# POWER.net
KiCad netlist of a schematic drawn in Altium Designer
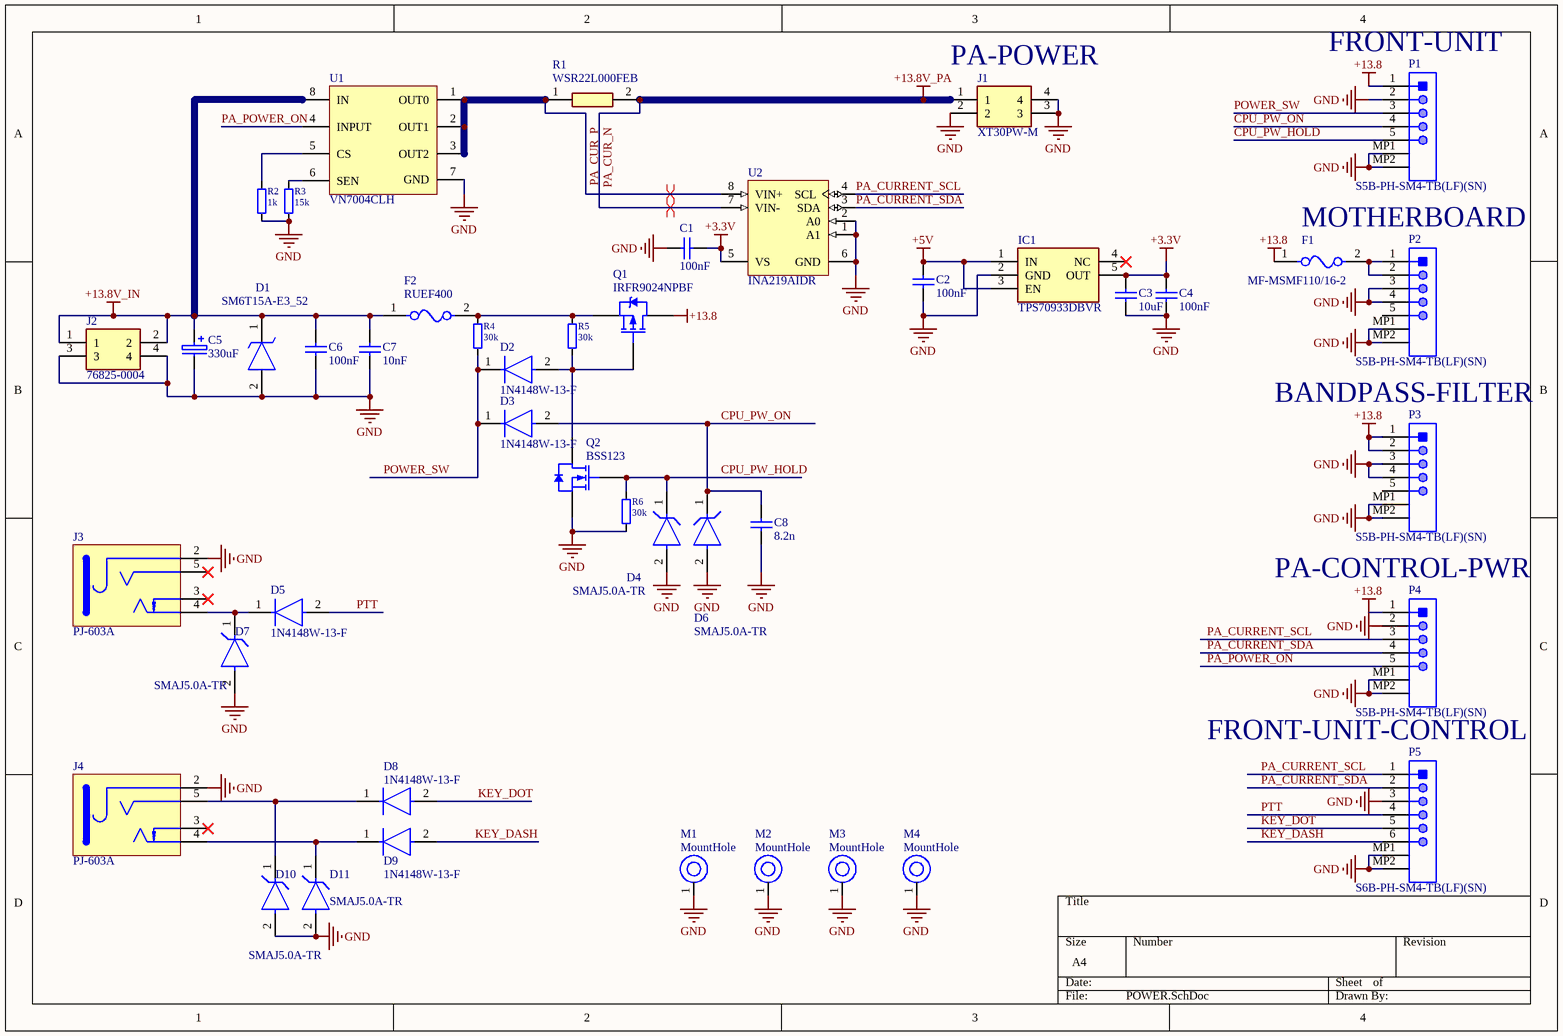
[diagram p0: POWER.SchDoc]

(export (version "E")
  (design (tool "Eeschema 10.0.6"))
  (components
    (comp (ref "C1")
      (value "100nF")
      (footprint "C-0805")
      (description "Ceramic Multilayer Capacitor")
      (fields (field (name "MANUFACTURER") "Yageo/Phycomp") (field (name "TOLERANCE") "±10%"))
      (libsource (lib "Hristo") (part "C semi"))
    )
    (comp (ref "C2")
      (value "100nF")
      (footprint "C-0805")
      (description "Ceramic Multilayer Capacitor")
      (fields (field (name "MANUFACTURER") "Yageo/Phycomp") (field (name "TOLERANCE") "±10%"))
      (libsource (lib "Hristo") (part "C semi"))
    )
    (comp (ref "C3")
      (value "10uF")
      (footprint "C-0805")
      (description "Ceramic Multilayer Capacitor")
      (fields (field (name "MANUFACTURER") "Yageo/Phycomp") (field (name "TOLERANCE") "±10%"))
      (libsource (lib "Hristo") (part "C semi"))
    )
    (comp (ref "C4")
      (value "100nF")
      (footprint "C-0805")
      (description "Ceramic Multilayer Capacitor")
      (fields (field (name "MANUFACTURER") "Yageo/Phycomp") (field (name "TOLERANCE") "±10%"))
      (libsource (lib "Hristo") (part "C semi"))
    )
    (comp (ref "C5")
      (value "330uF")
      (footprint "CE 5.0-10x12.5")
      (description "Capacitor Electrolytic")
      (fields (field (name "MANUFACTURER") "Yageo/Phycomp") (field (name "TOLERANCE") "±20%"))
      (libsource (lib "Hristo") (part "CE"))
    )
    (comp (ref "C6")
      (value "100nF")
      (footprint "C-0805")
      (description "Ceramic Multilayer Capacitor")
      (fields (field (name "MANUFACTURER") "Yageo/Phycomp") (field (name "TOLERANCE") "±10%"))
      (libsource (lib "Hristo") (part "C semi"))
    )
    (comp (ref "C7")
      (value "10nF")
      (footprint "C-0805")
      (description "Ceramic Multilayer Capacitor")
      (fields (field (name "MANUFACTURER") "Yageo/Phycomp") (field (name "TOLERANCE") "±10%"))
      (libsource (lib "Hristo") (part "C semi"))
    )
    (comp (ref "C8")
      (value "8.2n")
      (footprint "C-0805")
      (description "Ceramic Multilayer Capacitor")
      (fields (field (name "MANUFACTURER") "Yageo/Phycomp") (field (name "TOLERANCE") "±10%"))
      (libsource (lib "Hristo") (part "C semi"))
    )
    (comp (ref "D1")
      (value "SM6T15A-E3_52")
      (footprint "SamacSys:DIOM5436X244N")
      (description "TVS Diode (Uni-directional)")
      (fields
        (field (name "MANUFACTURER_PART_NUMBER") "SM6T15A-E3/52")
        (field (name "MOUSER PART NUMBER") "625-SM6T15A-E3")
      )
      (libsource (lib "*") (part "SM6T15A-E3_52"))
    )
    (comp (ref "D2")
      (value "1N4148W-13-F")
      (footprint "FP-SOD123-MFG")
      (description "DIODE GEN PURP 100V 150MA SOD123")
      (fields
        (field (name "OCTOPART") "https://octopart.com/1n4148w-13-f-diodes+inc.-2359612")
        (field (name "MANUFACTURER") "Diodes Inc.")
      )
      (libsource (lib "Altium Content Vault") (part "d7152d700b627762746794eb795d46e"))
    )
    (comp (ref "D3")
      (value "1N4148W-13-F")
      (footprint "FP-SOD123-MFG")
      (description "DIODE GEN PURP 100V 150MA SOD123")
      (fields
        (field (name "OCTOPART") "https://octopart.com/1n4148w-13-f-diodes+inc.-2359612")
        (field (name "MANUFACTURER") "Diodes Inc.")
      )
      (libsource (lib "Altium Content Vault") (part "d7152d700b627762746794eb795d46e"))
    )
    (comp (ref "D4")
      (value "SMAJ5.0A-TR")
      (footprint "FP-SMA-MFG")
      (description "TVS DIODE 5V 13.4V SMA")
      (fields
        (field (name "MANUFACTURER") "STMicroelectronics")
        (field (name "OCTOPART") "https://octopart.com/smaj5.0a-tr-stmicroelectronics-347063")
      )
      (libsource (lib "Altium Content Vault") (part "7ddec9f632b8482e96f7745d0fbdf39"))
    )
    (comp (ref "D5")
      (value "1N4148W-13-F")
      (footprint "FP-SOD123-MFG")
      (description "DIODE GEN PURP 100V 150MA SOD123")
      (fields
        (field (name "OCTOPART") "https://octopart.com/1n4148w-13-f-diodes+inc.-2359612")
        (field (name "MANUFACTURER") "Diodes Inc.")
      )
      (libsource (lib "Altium Content Vault") (part "d7152d700b627762746794eb795d46e"))
    )
    (comp (ref "D6")
      (value "SMAJ5.0A-TR")
      (footprint "FP-SMA-MFG")
      (description "TVS DIODE 5V 13.4V SMA")
      (fields
        (field (name "MANUFACTURER") "STMicroelectronics")
        (field (name "OCTOPART") "https://octopart.com/smaj5.0a-tr-stmicroelectronics-347063")
      )
      (libsource (lib "Altium Content Vault") (part "7ddec9f632b8482e96f7745d0fbdf39"))
    )
    (comp (ref "D7")
      (value "SMAJ5.0A-TR")
      (footprint "FP-SMA-MFG")
      (description "TVS DIODE 5V 13.4V SMA")
      (fields
        (field (name "MANUFACTURER") "STMicroelectronics")
        (field (name "OCTOPART") "https://octopart.com/smaj5.0a-tr-stmicroelectronics-347063")
      )
      (libsource (lib "Altium Content Vault") (part "7ddec9f632b8482e96f7745d0fbdf39"))
    )
    (comp (ref "D8")
      (value "1N4148W-13-F")
      (footprint "FP-SOD123-MFG")
      (description "DIODE GEN PURP 100V 150MA SOD123")
      (fields
        (field (name "OCTOPART") "https://octopart.com/1n4148w-13-f-diodes+inc.-2359612")
        (field (name "MANUFACTURER") "Diodes Inc.")
      )
      (libsource (lib "Altium Content Vault") (part "d7152d700b627762746794eb795d46e"))
    )
    (comp (ref "D9")
      (value "1N4148W-13-F")
      (footprint "FP-SOD123-MFG")
      (description "DIODE GEN PURP 100V 150MA SOD123")
      (fields
        (field (name "OCTOPART") "https://octopart.com/1n4148w-13-f-diodes+inc.-2359612")
        (field (name "MANUFACTURER") "Diodes Inc.")
      )
      (libsource (lib "Altium Content Vault") (part "d7152d700b627762746794eb795d46e"))
    )
    (comp (ref "D10")
      (value "SMAJ5.0A-TR")
      (footprint "FP-SMA-MFG")
      (description "TVS DIODE 5V 13.4V SMA")
      (fields
        (field (name "MANUFACTURER") "STMicroelectronics")
        (field (name "OCTOPART") "https://octopart.com/smaj5.0a-tr-stmicroelectronics-347063")
      )
      (libsource (lib "Altium Content Vault") (part "7ddec9f632b8482e96f7745d0fbdf39"))
    )
    (comp (ref "D11")
      (value "SMAJ5.0A-TR")
      (footprint "FP-SMA-MFG")
      (description "TVS DIODE 5V 13.4V SMA")
      (fields
        (field (name "MANUFACTURER") "STMicroelectronics")
        (field (name "OCTOPART") "https://octopart.com/smaj5.0a-tr-stmicroelectronics-347063")
      )
      (libsource (lib "Altium Content Vault") (part "7ddec9f632b8482e96f7745d0fbdf39"))
    )
    (comp (ref "F1")
      (value "MF-MSMF110/16-2")
      (footprint "FP-MF-MSMF110-16-MFG")
      (description "PTC RESET FUSE 16V 1.1A 1812")
      (fields
        (field (name "OCTOPART") "https://octopart.com/mf-msmf110%2F16-2-bourns-40767")
        (field (name "MANUFACTURER") "Bourns")
      )
      (libsource (lib "Altium Content Vault") (part "5bcf9b9f640e542cf0359d10258e979"))
    )
    (comp (ref "F2")
      (value "RUEF400")
      (footprint "FP-RUEF400-MFG")
      (description "PTC RESET FUSE 30V 4A RADIAL")
      (fields
        (field (name "MANUFACTURER") "Littelfuse")
        (field (name "OCTOPART") "https://octopart.com/ruef400-littelfuse-74215791")
      )
      (libsource (lib "Altium Content Vault") (part "5bcf9b9f640e542cf0359d10258e979"))
    )
    (comp (ref "IC1")
      (value "TPS70933DBVR")
      (footprint "SamacSys:SOT95P280X145-5N")
      (description "Integrated Circuit")
      (fields (field (name "MOUSER PART NUMBER") "595-TPS70933DBVR"))
      (libsource (lib "*") (part "TPS70933DBVR"))
    )
    (comp (ref "J1")
      (value "XT30PW-M")
      (footprint "SamacSys:XT30PWM")
      (description "Connector")
      (libsource (lib "*") (part "XT30PW-M"))
    )
    (comp (ref "J2")
      (value "76825-0004")
      (footprint "SamacSys:768250004")
      (description "Connector")
      (fields (field (name "MOUSER2 PART NUMBER") "538-76825-0004"))
      (libsource (lib "*") (part "76825-0004"))
    )
    (comp (ref "J3") (value "PJ-603A") (footprint "PJ-603A") (libsource (lib "Hristo") (part "PJ-603A")))
    (comp (ref "J4") (value "PJ-603A") (footprint "PJ-603A") (libsource (lib "Hristo") (part "PJ-603A")))
    (comp (ref "M1")
      (value "MountHole")
      (footprint "MountHole")
      (libsource (lib "Hristo") (part "MountHole"))
    )
    (comp (ref "M2")
      (value "MountHole")
      (footprint "MountHole")
      (libsource (lib "Hristo") (part "MountHole"))
    )
    (comp (ref "M3")
      (value "MountHole")
      (footprint "MountHole")
      (libsource (lib "Hristo") (part "MountHole"))
    )
    (comp (ref "M4")
      (value "MountHole")
      (footprint "MountHole")
      (libsource (lib "Hristo") (part "MountHole"))
    )
    (comp (ref "P1")
      (value "S5B-PH-SM4-TB(LF)(SN)")
      (footprint "JST-S5B-PH-SM4-TB_V")
      (description "Male Header, Pitch 2 mm, 1 x 5 Position, Height 5.5 mm, -25 to 85 degC, RoHS, Tape and Reel")
      (fields (field (name "MANUFACTURER") "JST"))
      (libsource (lib "Altium Content Vault") (part "CN-1P-2M-R5"))
    )
    (comp (ref "P2")
      (value "S5B-PH-SM4-TB(LF)(SN)")
      (footprint "JST-S5B-PH-SM4-TB_V")
      (description "Male Header, Pitch 2 mm, 1 x 5 Position, Height 5.5 mm, -25 to 85 degC, RoHS, Tape and Reel")
      (fields (field (name "MANUFACTURER") "JST"))
      (libsource (lib "Altium Content Vault") (part "CN-1P-2M-R5"))
    )
    (comp (ref "P3")
      (value "S5B-PH-SM4-TB(LF)(SN)")
      (footprint "JST-S5B-PH-SM4-TB_V")
      (description "Male Header, Pitch 2 mm, 1 x 5 Position, Height 5.5 mm, -25 to 85 degC, RoHS, Tape and Reel")
      (fields (field (name "MANUFACTURER") "JST"))
      (libsource (lib "Altium Content Vault") (part "CN-1P-2M-R5"))
    )
    (comp (ref "P4")
      (value "S5B-PH-SM4-TB(LF)(SN)")
      (footprint "JST-S5B-PH-SM4-TB_V")
      (description "Male Header, Pitch 2 mm, 1 x 5 Position, Height 5.5 mm, -25 to 85 degC, RoHS, Tape and Reel")
      (fields (field (name "MANUFACTURER") "JST"))
      (libsource (lib "Altium Content Vault") (part "CN-1P-2M-R5"))
    )
    (comp (ref "P5")
      (value "S6B-PH-SM4-TB(LF)(SN)")
      (footprint "JST-S6B-PH-SM4-TB(LF)(SN)_V")
      (description "Male Header, Pitch 2 mm, 1 x 6 Position, Height 5.5 mm, -25 to 85 degC")
      (fields (field (name "MANUFACTURER") "JST"))
      (libsource (lib "Altium Content Vault") (part "CN-1P-2M-R6"))
    )
    (comp (ref "Q1")
      (value "IRFR9024NPBF")
      (footprint "ONSC-DPAK-3-369C-01_V")
      (description "IRFR9024NPBF, Транзистор, Р-канал 55В 11А")
      (fields (field (name "MANUFACTURER") "On Semiconductor") (field (name "PARTNUMBER") "NTD2955G"))
      (libsource (lib "Altium Content Vault") (part "ONSC-PMOS-G1S3D4-3_B"))
    )
    (comp (ref "Q2")
      (value "BSS123")
      (footprint "FAIR-SOT23-3_V")
      (fields (field (name "MANUFACTURER") "Fairchild"))
      (libsource (lib "Altium Content Vault") (part "NEMOS-GSD-3"))
    )
    (comp (ref "R1")
      (value "WSR22L000FEB")
      (footprint "SamacSys:RESM11670X254N")
      (description "Resistor")
      (fields
        (field (name "MANUFACTURER_PART_NUMBER") "WSR21L000FEA")
        (field (name "MOUSER PART NUMBER") "71-WSR21L000FEA")
      )
      (libsource (lib "*") (part "WSR21L000FEA"))
    )
    (comp (ref "R2")
      (value "1k")
      (footprint "R-0805")
      (description "Chip Resistor")
      (fields (field (name "MANUFACTURER") "Yageo/Phycomp"))
      (libsource (lib "Hristo") (part "RES semi"))
    )
    (comp (ref "R3")
      (value "15k")
      (footprint "R-0805")
      (description "Chip Resistor")
      (fields (field (name "MANUFACTURER") "Yageo/Phycomp"))
      (libsource (lib "Hristo") (part "RES semi"))
    )
    (comp (ref "R4")
      (value "30k")
      (footprint "R-0805")
      (description "Chip Resistor")
      (fields (field (name "MANUFACTURER") "Yageo/Phycomp"))
      (libsource (lib "Hristo") (part "RES semi"))
    )
    (comp (ref "R5")
      (value "30k")
      (footprint "R-0805")
      (description "Chip Resistor")
      (fields (field (name "MANUFACTURER") "Yageo/Phycomp"))
      (libsource (lib "Hristo") (part "RES semi"))
    )
    (comp (ref "R6")
      (value "30k")
      (footprint "R-0805")
      (description "Chip Resistor")
      (fields (field (name "MANUFACTURER") "Yageo/Phycomp"))
      (libsource (lib "Hristo") (part "RES semi"))
    )
    (comp (ref "U1")
      (value "VN7004CLH")
      (footprint "OctaPAK7_6P1X6P5_STM-M")
      (libsource (lib "Hristo") (part "VN7004CLH"))
    )
    (comp (ref "U2")
      (value "INA219AIDR")
      (footprint "D0008A_L")
      (fields (field (name "MANUFACTURER") "Texas Instruments"))
      (libsource (lib "Altium Content Vault") (part "TI-INA219D8"))
    )
  )
  (nets
    (net (code "1") (name "+3.3V") (class "Default")
      (node (ref "C1") (pin "1") (pinfunction "1_1") (pintype "passive"))
      (node (ref "C3") (pin "1") (pinfunction "1_1") (pintype "passive"))
      (node (ref "C4") (pin "1") (pinfunction "1_1") (pintype "passive"))
      (node (ref "IC1") (pin "5") (pinfunction "OUT_5") (pintype "passive"))
      (node (ref "U2") (pin "5") (pinfunction "VS_5") (pintype "power_in"))
    )
    (net (code "2") (name "+5V") (class "Default")
      (node (ref "C2") (pin "1") (pinfunction "1_1") (pintype "passive"))
      (node (ref "IC1") (pin "1") (pinfunction "IN_1") (pintype "passive"))
      (node (ref "IC1") (pin "3") (pinfunction "EN_3") (pintype "passive"))
    )
    (net (code "3") (name "+13.8") (class "Default")
      (node (ref "F1") (pin "1") (pinfunction "1_1") (pintype "passive"))
      (node (ref "P1") (pin "1") (pinfunction "1_1") (pintype "passive"))
      (node (ref "P3") (pin "1") (pinfunction "1_1") (pintype "passive"))
      (node (ref "P3") (pin "2") (pinfunction "2_2") (pintype "passive"))
      (node (ref "P4") (pin "1") (pinfunction "1_1") (pintype "passive"))
      (node (ref "Q1") (pin "4") (pinfunction "D_4") (pintype "passive"))
    )
    (net (code "4") (name "+13.8V_IN") (class "Default")
      (node (ref "C5") (pin "1") (pintype "passive"))
      (node (ref "C6") (pin "1") (pinfunction "1_1") (pintype "passive"))
      (node (ref "C7") (pin "1") (pinfunction "1_1") (pintype "passive"))
      (node (ref "D1") (pin "1") (pinfunction "K_1") (pintype "passive"))
      (node (ref "F2") (pin "1") (pinfunction "1_1") (pintype "passive"))
      (node (ref "J2") (pin "1") (pinfunction "1_1") (pintype "passive"))
      (node (ref "J2") (pin "2") (pinfunction "2_2") (pintype "passive"))
      (node (ref "U1") (pin "8") (pinfunction "IN_8") (pintype "passive"))
    )
    (net (code "5") (name "+13.8V_PA") (class "Default")
      (node (ref "J1") (pin "1") (pinfunction "1_1") (pintype "passive"))
      (node (ref "R1") (pin "2") (pinfunction "2_2") (pintype "passive"))
      (node (ref "U2") (pin "7") (pinfunction "VIN-_7") (pintype "input"))
    )
    (net (code "6") (name "/CPU_PW_HOLD") (class "Default")
      (node (ref "D4") (pin "1") (pinfunction "K_1") (pintype "passive"))
      (node (ref "P1") (pin "5") (pinfunction "5_5") (pintype "passive"))
      (node (ref "Q2") (pin "1") (pinfunction "G_1") (pintype "passive"))
      (node (ref "R6") (pin "2") (pinfunction "2_2") (pintype "passive"))
    )
    (net (code "7") (name "/CPU_PW_ON") (class "Default")
      (node (ref "C8") (pin "1") (pinfunction "1_1") (pintype "passive"))
      (node (ref "D3") (pin "2") (pinfunction "A_2") (pintype "passive"))
      (node (ref "D6") (pin "1") (pinfunction "K_1") (pintype "passive"))
      (node (ref "P1") (pin "4") (pinfunction "4_4") (pintype "passive"))
    )
    (net (code "8") (name "/KEY_DASH") (class "Default")
      (node (ref "D9") (pin "2") (pinfunction "A_2") (pintype "passive"))
      (node (ref "P5") (pin "6") (pinfunction "6_6") (pintype "passive"))
    )
    (net (code "9") (name "/KEY_DOT") (class "Default")
      (node (ref "D8") (pin "2") (pinfunction "A_2") (pintype "passive"))
      (node (ref "P5") (pin "5") (pinfunction "5_5") (pintype "passive"))
    )
    (net (code "10") (name "/PA_CURRENT_SCL") (class "Default")
      (node (ref "P4") (pin "3") (pinfunction "3_3") (pintype "passive"))
      (node (ref "P5") (pin "1") (pinfunction "1_1") (pintype "passive"))
      (node (ref "U2") (pin "4") (pinfunction "SCL_4") (pintype "bidirectional"))
    )
    (net (code "11") (name "/PA_CURRENT_SDA") (class "Default")
      (node (ref "P4") (pin "4") (pinfunction "4_4") (pintype "passive"))
      (node (ref "P5") (pin "2") (pinfunction "2_2") (pintype "passive"))
      (node (ref "U2") (pin "3") (pinfunction "SDA_3") (pintype "bidirectional"))
    )
    (net (code "12") (name "/PA_CUR_P") (class "Default")
      (node (ref "R1") (pin "1") (pinfunction "1_1") (pintype "passive"))
      (node (ref "U1") (pin "1") (pinfunction "OUT0_1") (pintype "passive"))
      (node (ref "U1") (pin "2") (pinfunction "OUT1_2") (pintype "passive"))
      (node (ref "U1") (pin "3") (pinfunction "OUT2_3") (pintype "passive"))
      (node (ref "U2") (pin "8") (pinfunction "VIN+_8") (pintype "input"))
    )
    (net (code "13") (name "/PA_POWER_ON") (class "Default")
      (node (ref "P4") (pin "5") (pinfunction "5_5") (pintype "passive"))
      (node (ref "U1") (pin "4") (pinfunction "INPUT_4") (pintype "passive"))
    )
    (net (code "14") (name "/POWER_SW") (class "Default")
      (node (ref "D2") (pin "1") (pinfunction "C_1") (pintype "passive"))
      (node (ref "D3") (pin "1") (pinfunction "C_1") (pintype "passive"))
      (node (ref "P1") (pin "3") (pinfunction "3_3") (pintype "passive"))
      (node (ref "R4") (pin "1") (pinfunction "1_1") (pintype "passive"))
    )
    (net (code "15") (name "/PTT") (class "Default")
      (node (ref "D5") (pin "2") (pinfunction "A_2") (pintype "passive"))
      (node (ref "P5") (pin "4") (pinfunction "4_4") (pintype "passive"))
    )
    (net (code "16") (name "GND") (class "Default")
      (node (ref "C1") (pin "2") (pinfunction "2_2") (pintype "passive"))
      (node (ref "C2") (pin "2") (pinfunction "2_2") (pintype "passive"))
      (node (ref "C3") (pin "2") (pinfunction "2_2") (pintype "passive"))
      (node (ref "C4") (pin "2") (pinfunction "2_2") (pintype "passive"))
      (node (ref "C5") (pin "2") (pintype "passive"))
      (node (ref "C6") (pin "2") (pinfunction "2_2") (pintype "passive"))
      (node (ref "C7") (pin "2") (pinfunction "2_2") (pintype "passive"))
      (node (ref "C8") (pin "2") (pinfunction "2_2") (pintype "passive"))
      (node (ref "D1") (pin "2") (pinfunction "A_2") (pintype "passive"))
      (node (ref "D10") (pin "2") (pinfunction "A_2") (pintype "passive"))
      (node (ref "D11") (pin "2") (pinfunction "A_2") (pintype "passive"))
      (node (ref "D4") (pin "2") (pinfunction "A_2") (pintype "passive"))
      (node (ref "D6") (pin "2") (pinfunction "A_2") (pintype "passive"))
      (node (ref "D7") (pin "2") (pinfunction "A_2") (pintype "passive"))
      (node (ref "IC1") (pin "2") (pinfunction "GND_2") (pintype "passive"))
      (node (ref "J1") (pin "2") (pinfunction "2_2") (pintype "passive"))
      (node (ref "J1") (pin "3") (pinfunction "3_3") (pintype "passive"))
      (node (ref "J1") (pin "4") (pinfunction "4_4") (pintype "passive"))
      (node (ref "J2") (pin "3") (pinfunction "3_3") (pintype "passive"))
      (node (ref "J2") (pin "4") (pinfunction "4_4") (pintype "passive"))
      (node (ref "J3") (pin "2") (pintype "power_in"))
      (node (ref "J4") (pin "2") (pintype "power_in"))
      (node (ref "M1") (pin "1") (pintype "passive"))
      (node (ref "M2") (pin "1") (pintype "passive"))
      (node (ref "M3") (pin "1") (pintype "passive"))
      (node (ref "M4") (pin "1") (pintype "passive"))
      (node (ref "P1") (pin "2") (pinfunction "2_2") (pintype "passive"))
      (node (ref "P1") (pin "MP1") (pinfunction "MP1_MP1") (pintype "passive"))
      (node (ref "P1") (pin "MP2") (pinfunction "MP2_MP2") (pintype "passive"))
      (node (ref "P2") (pin "3") (pinfunction "3_3") (pintype "passive"))
      (node (ref "P2") (pin "4") (pinfunction "4_4") (pintype "passive"))
      (node (ref "P2") (pin "MP1") (pinfunction "MP1_MP1") (pintype "passive"))
      (node (ref "P2") (pin "MP2") (pinfunction "MP2_MP2") (pintype "passive"))
      (node (ref "P3") (pin "3") (pinfunction "3_3") (pintype "passive"))
      (node (ref "P3") (pin "4") (pinfunction "4_4") (pintype "passive"))
      (node (ref "P3") (pin "MP1") (pinfunction "MP1_MP1") (pintype "passive"))
      (node (ref "P3") (pin "MP2") (pinfunction "MP2_MP2") (pintype "passive"))
      (node (ref "P4") (pin "2") (pinfunction "2_2") (pintype "passive"))
      (node (ref "P4") (pin "MP1") (pinfunction "MP1_MP1") (pintype "passive"))
      (node (ref "P4") (pin "MP2") (pinfunction "MP2_MP2") (pintype "passive"))
      (node (ref "P5") (pin "3") (pinfunction "3_3") (pintype "passive"))
      (node (ref "P5") (pin "MP1") (pinfunction "MP1_MP1") (pintype "passive"))
      (node (ref "P5") (pin "MP2") (pinfunction "MP2_MP2") (pintype "passive"))
      (node (ref "Q2") (pin "2") (pinfunction "S_2") (pintype "passive"))
      (node (ref "R2") (pin "1") (pinfunction "1_1") (pintype "passive"))
      (node (ref "R3") (pin "1") (pinfunction "1_1") (pintype "passive"))
      (node (ref "R6") (pin "1") (pinfunction "1_1") (pintype "passive"))
      (node (ref "U1") (pin "7") (pinfunction "GND_7") (pintype "passive"))
      (node (ref "U2") (pin "1") (pinfunction "A1_1") (pintype "input"))
      (node (ref "U2") (pin "2") (pinfunction "A0_2") (pintype "input"))
      (node (ref "U2") (pin "6") (pinfunction "GND_6") (pintype "power_in"))
    )
    (net (code "17") (name "Net-(D2-A)") (class "Default")
      (node (ref "D2") (pin "2") (pinfunction "A_2") (pintype "passive"))
      (node (ref "Q1") (pin "1") (pinfunction "G_1") (pintype "passive"))
      (node (ref "Q2") (pin "3") (pinfunction "D_3") (pintype "passive"))
      (node (ref "R5") (pin "1") (pinfunction "1_1") (pintype "passive"))
    )
    (net (code "18") (name "Net-(D5-C)") (class "Default")
      (node (ref "D5") (pin "1") (pinfunction "C_1") (pintype "passive"))
      (node (ref "D7") (pin "1") (pinfunction "K_1") (pintype "passive"))
      (node (ref "J3") (pin "4") (pintype "power_in"))
    )
    (net (code "19") (name "Net-(D10-K)") (class "Default")
      (node (ref "D10") (pin "1") (pinfunction "K_1") (pintype "passive"))
      (node (ref "D8") (pin "1") (pinfunction "C_1") (pintype "passive"))
      (node (ref "J4") (pin "5") (pintype "power_in"))
    )
    (net (code "20") (name "Net-(D11-K)") (class "Default")
      (node (ref "D11") (pin "1") (pinfunction "K_1") (pintype "passive"))
      (node (ref "D9") (pin "1") (pinfunction "C_1") (pintype "passive"))
      (node (ref "J4") (pin "4") (pintype "power_in"))
    )
    (net (code "21") (name "Net-(F1-Pad2)") (class "Default")
      (node (ref "F1") (pin "2") (pinfunction "2_2") (pintype "passive"))
      (node (ref "P2") (pin "1") (pinfunction "1_1") (pintype "passive"))
      (node (ref "P2") (pin "2") (pinfunction "2_2") (pintype "passive"))
    )
    (net (code "22") (name "Net-(Q1-S)") (class "Default")
      (node (ref "F2") (pin "2") (pinfunction "2_2") (pintype "passive"))
      (node (ref "Q1") (pin "3") (pinfunction "S_3") (pintype "passive"))
      (node (ref "R4") (pin "2") (pinfunction "2_2") (pintype "passive"))
      (node (ref "R5") (pin "2") (pinfunction "2_2") (pintype "passive"))
    )
    (net (code "23") (name "Net-(U1-CS)") (class "Default")
      (node (ref "R2") (pin "2") (pinfunction "2_2") (pintype "passive"))
      (node (ref "U1") (pin "5") (pinfunction "CS_5") (pintype "passive"))
    )
    (net (code "24") (name "Net-(U1-SEN)") (class "Default")
      (node (ref "R3") (pin "2") (pinfunction "2_2") (pintype "passive"))
      (node (ref "U1") (pin "6") (pinfunction "SEN_6") (pintype "passive"))
    )
    (net (code "25") (name "unconnected-(IC1-NC-Pad4)") (class "Default")
      (node (ref "IC1") (pin "4") (pinfunction "NC_4") (pintype "passive+no_connect"))
    )
    (net (code "26") (name "unconnected-(J3-Pad3)") (class "Default")
      (node (ref "J3") (pin "3") (pintype "power_in+no_connect"))
    )
    (net (code "27") (name "unconnected-(J3-Pad5)") (class "Default")
      (node (ref "J3") (pin "5") (pintype "power_in+no_connect"))
    )
    (net (code "28") (name "unconnected-(J4-Pad3)") (class "Default")
      (node (ref "J4") (pin "3") (pintype "power_in+no_connect"))
    )
    (net (code "29") (name "unconnected-(P2-Pad5)") (class "Default")
      (node (ref "P2") (pin "5") (pinfunction "5_5") (pintype "passive"))
    )
    (net (code "30") (name "unconnected-(P3-Pad5)") (class "Default")
      (node (ref "P3") (pin "5") (pinfunction "5_5") (pintype "passive"))
    )
  )
)
